# ads-b.net
KiCad netlist of a schematic drawn in EAGLE
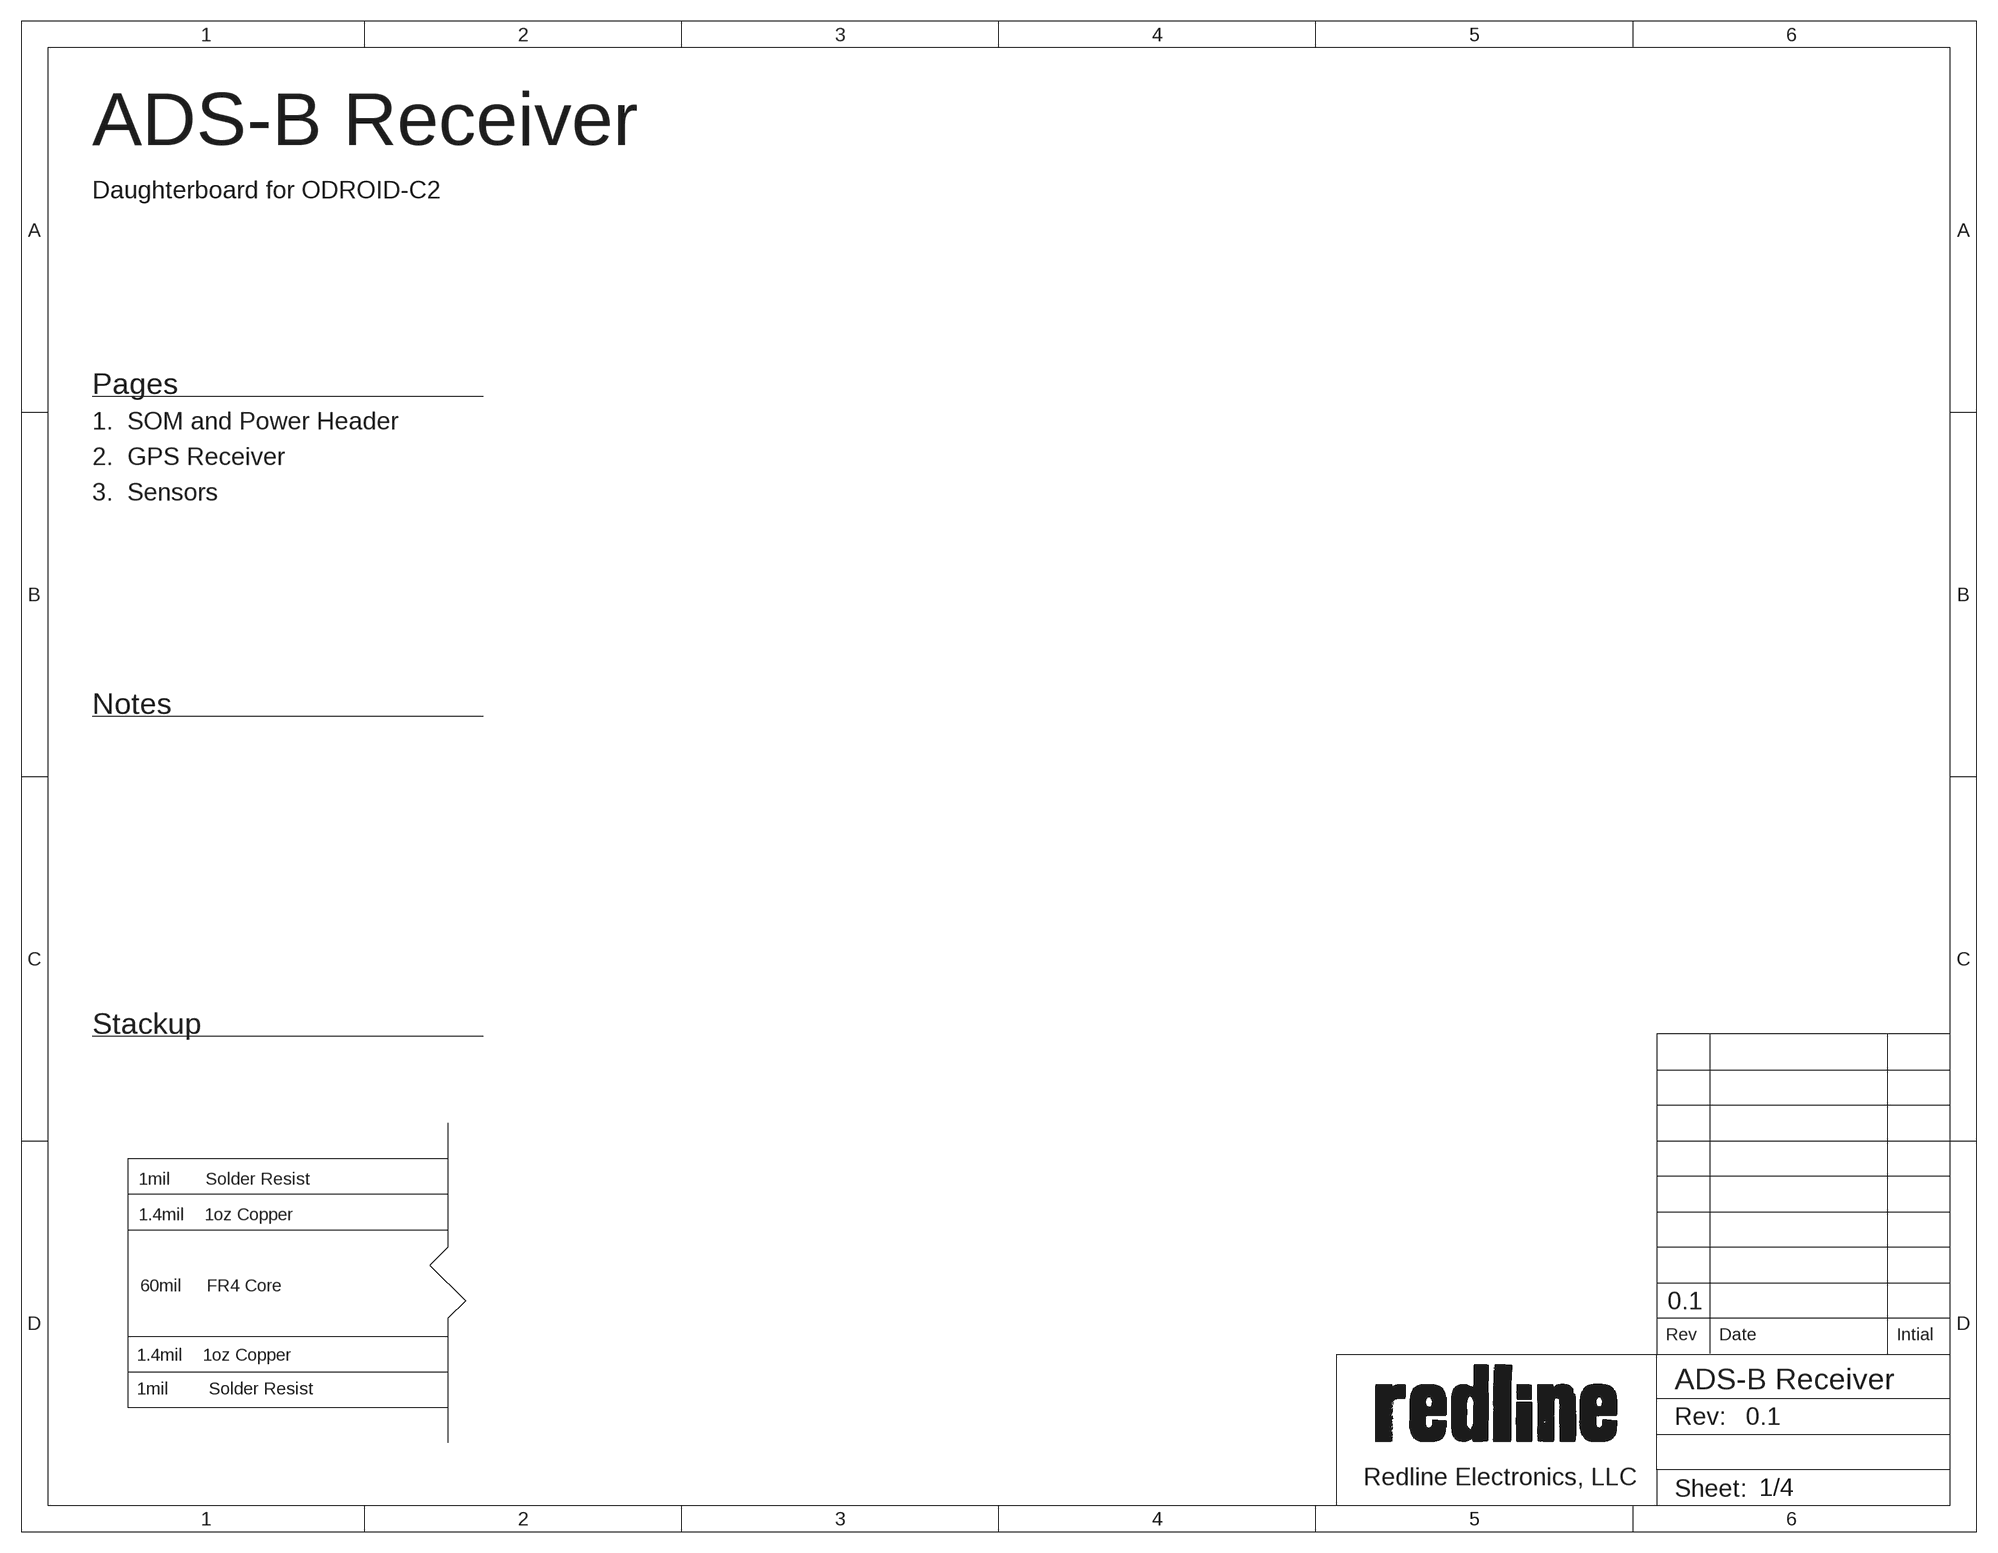
[diagram p0: schematic, sheet 1]
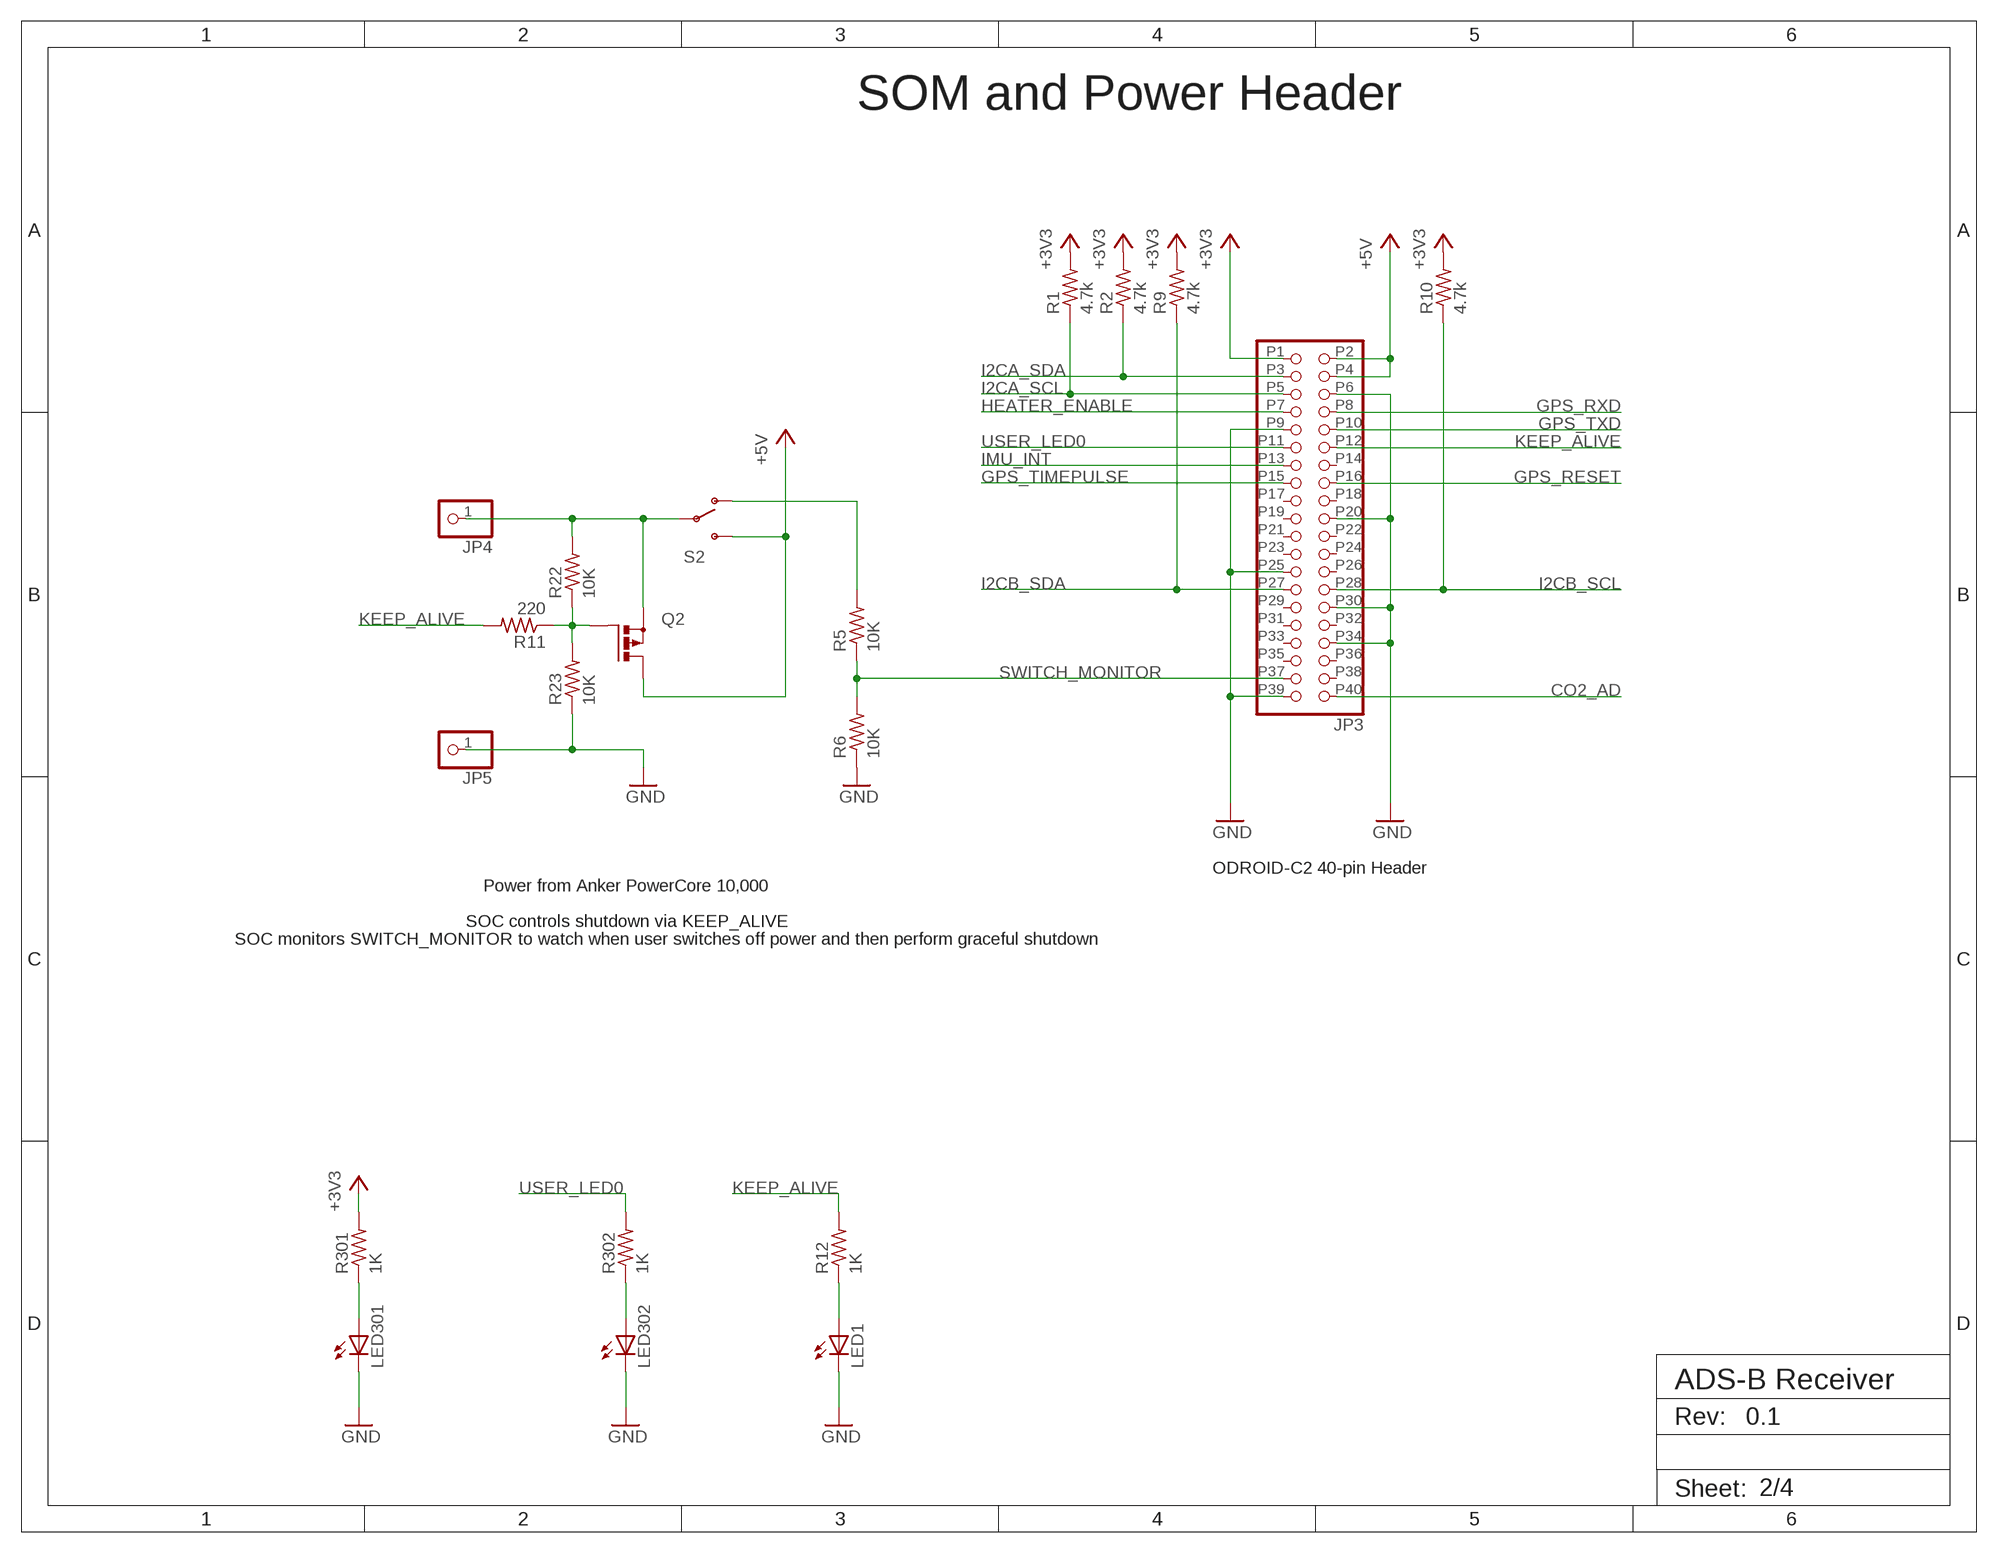
[diagram p1: schematic, sheet 2]
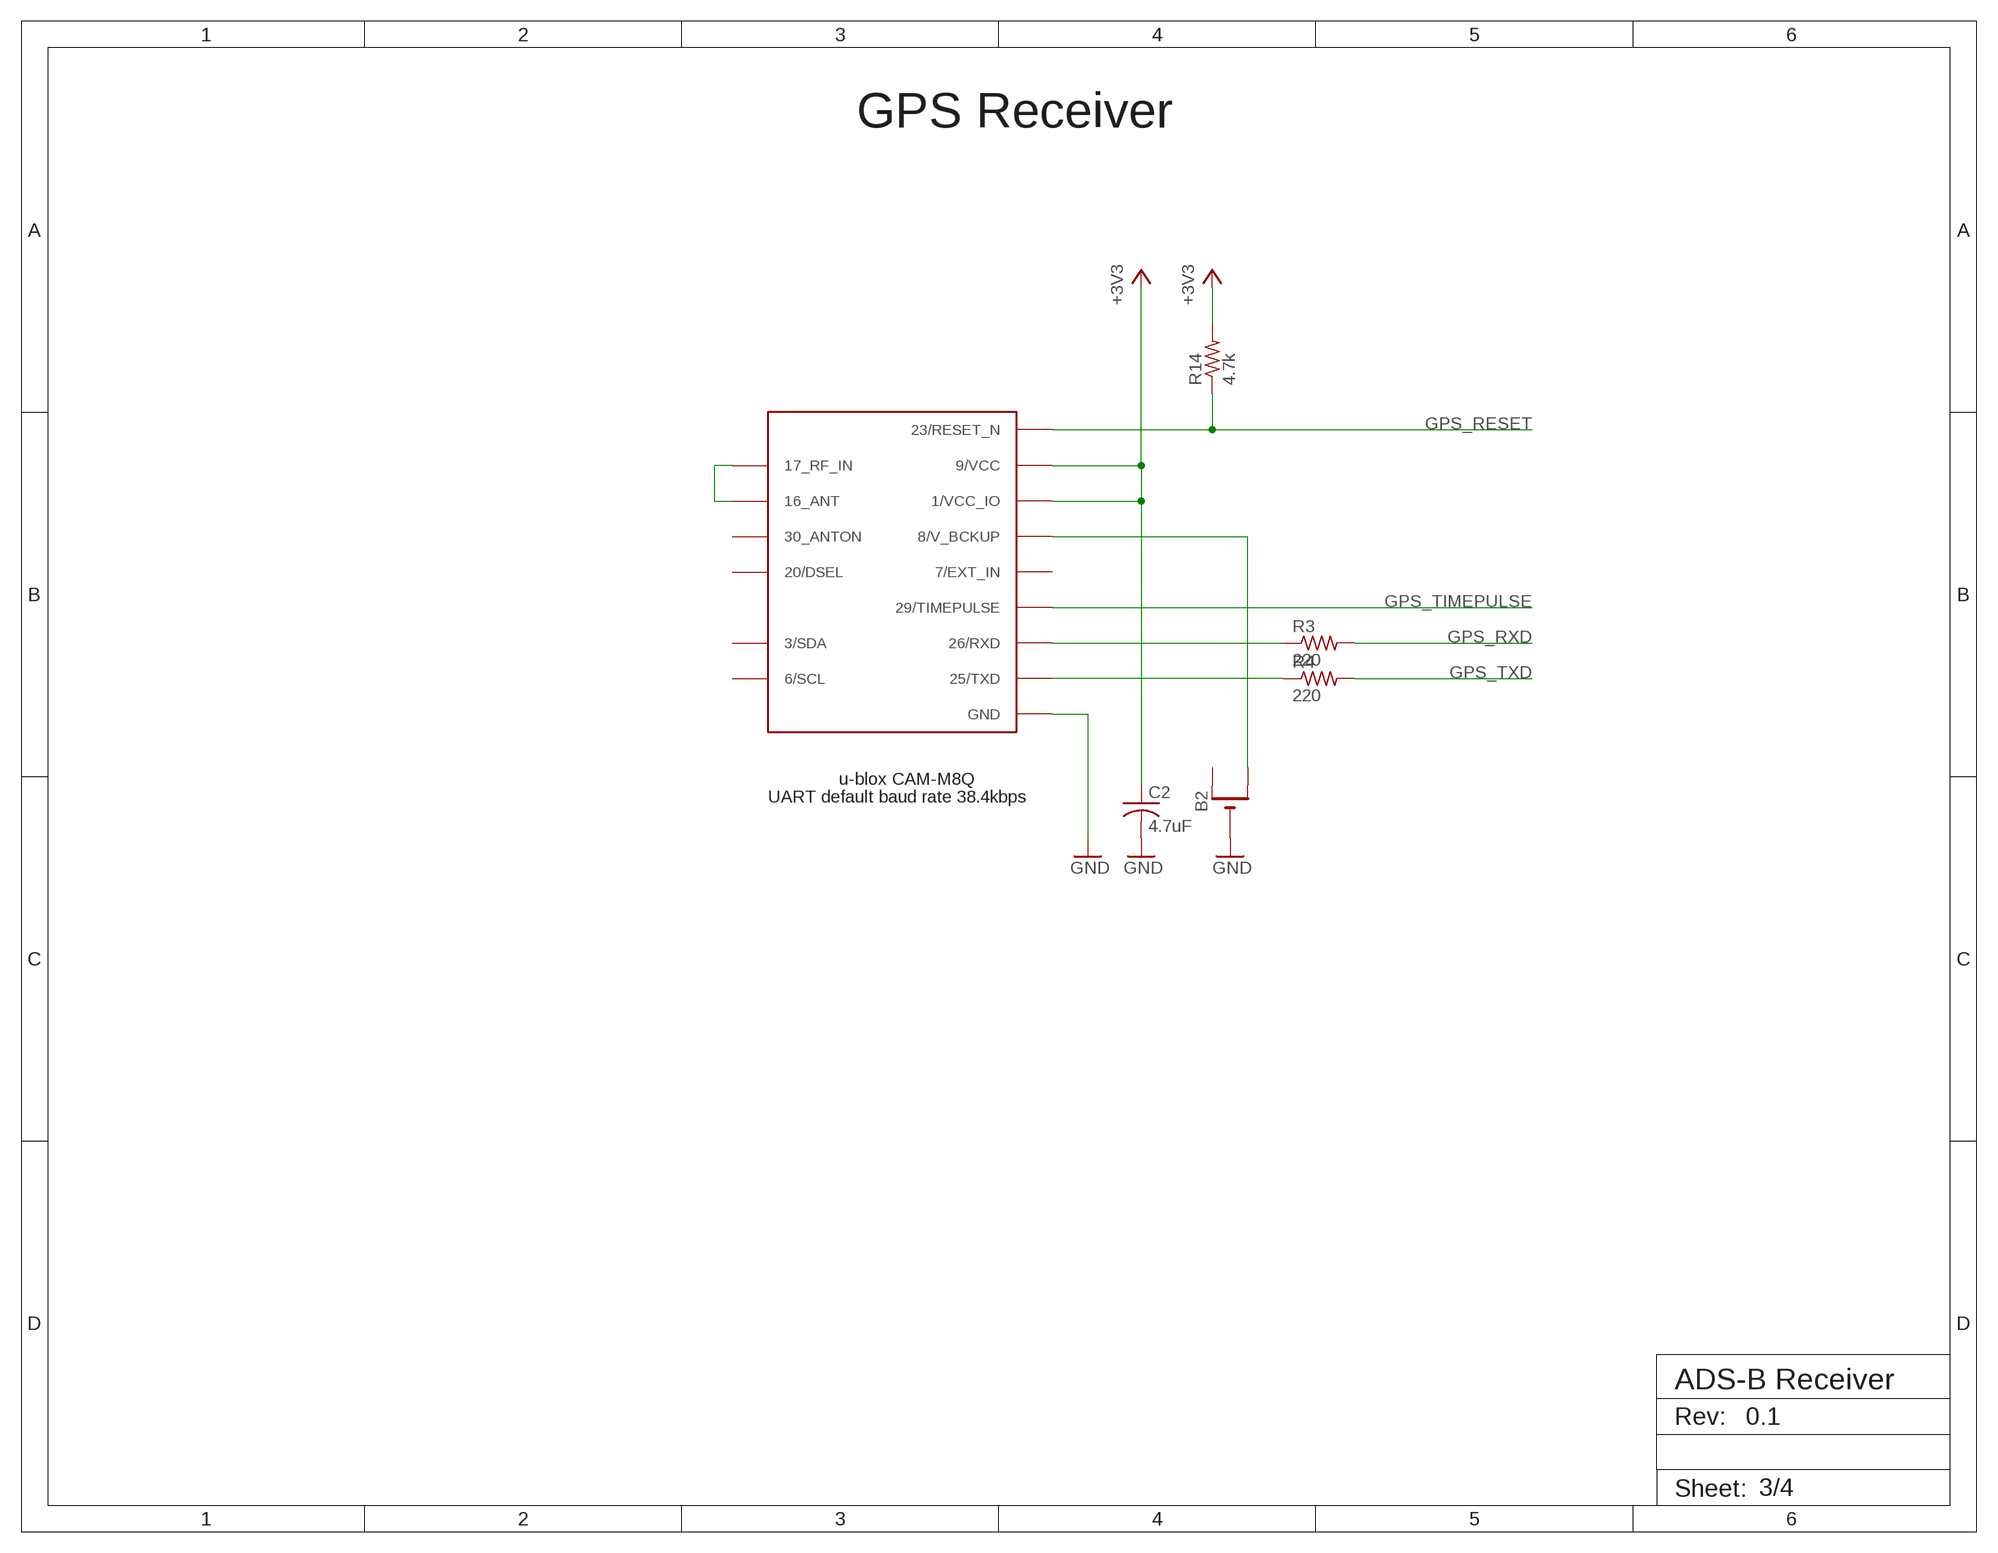
[diagram p2: schematic, sheet 3]
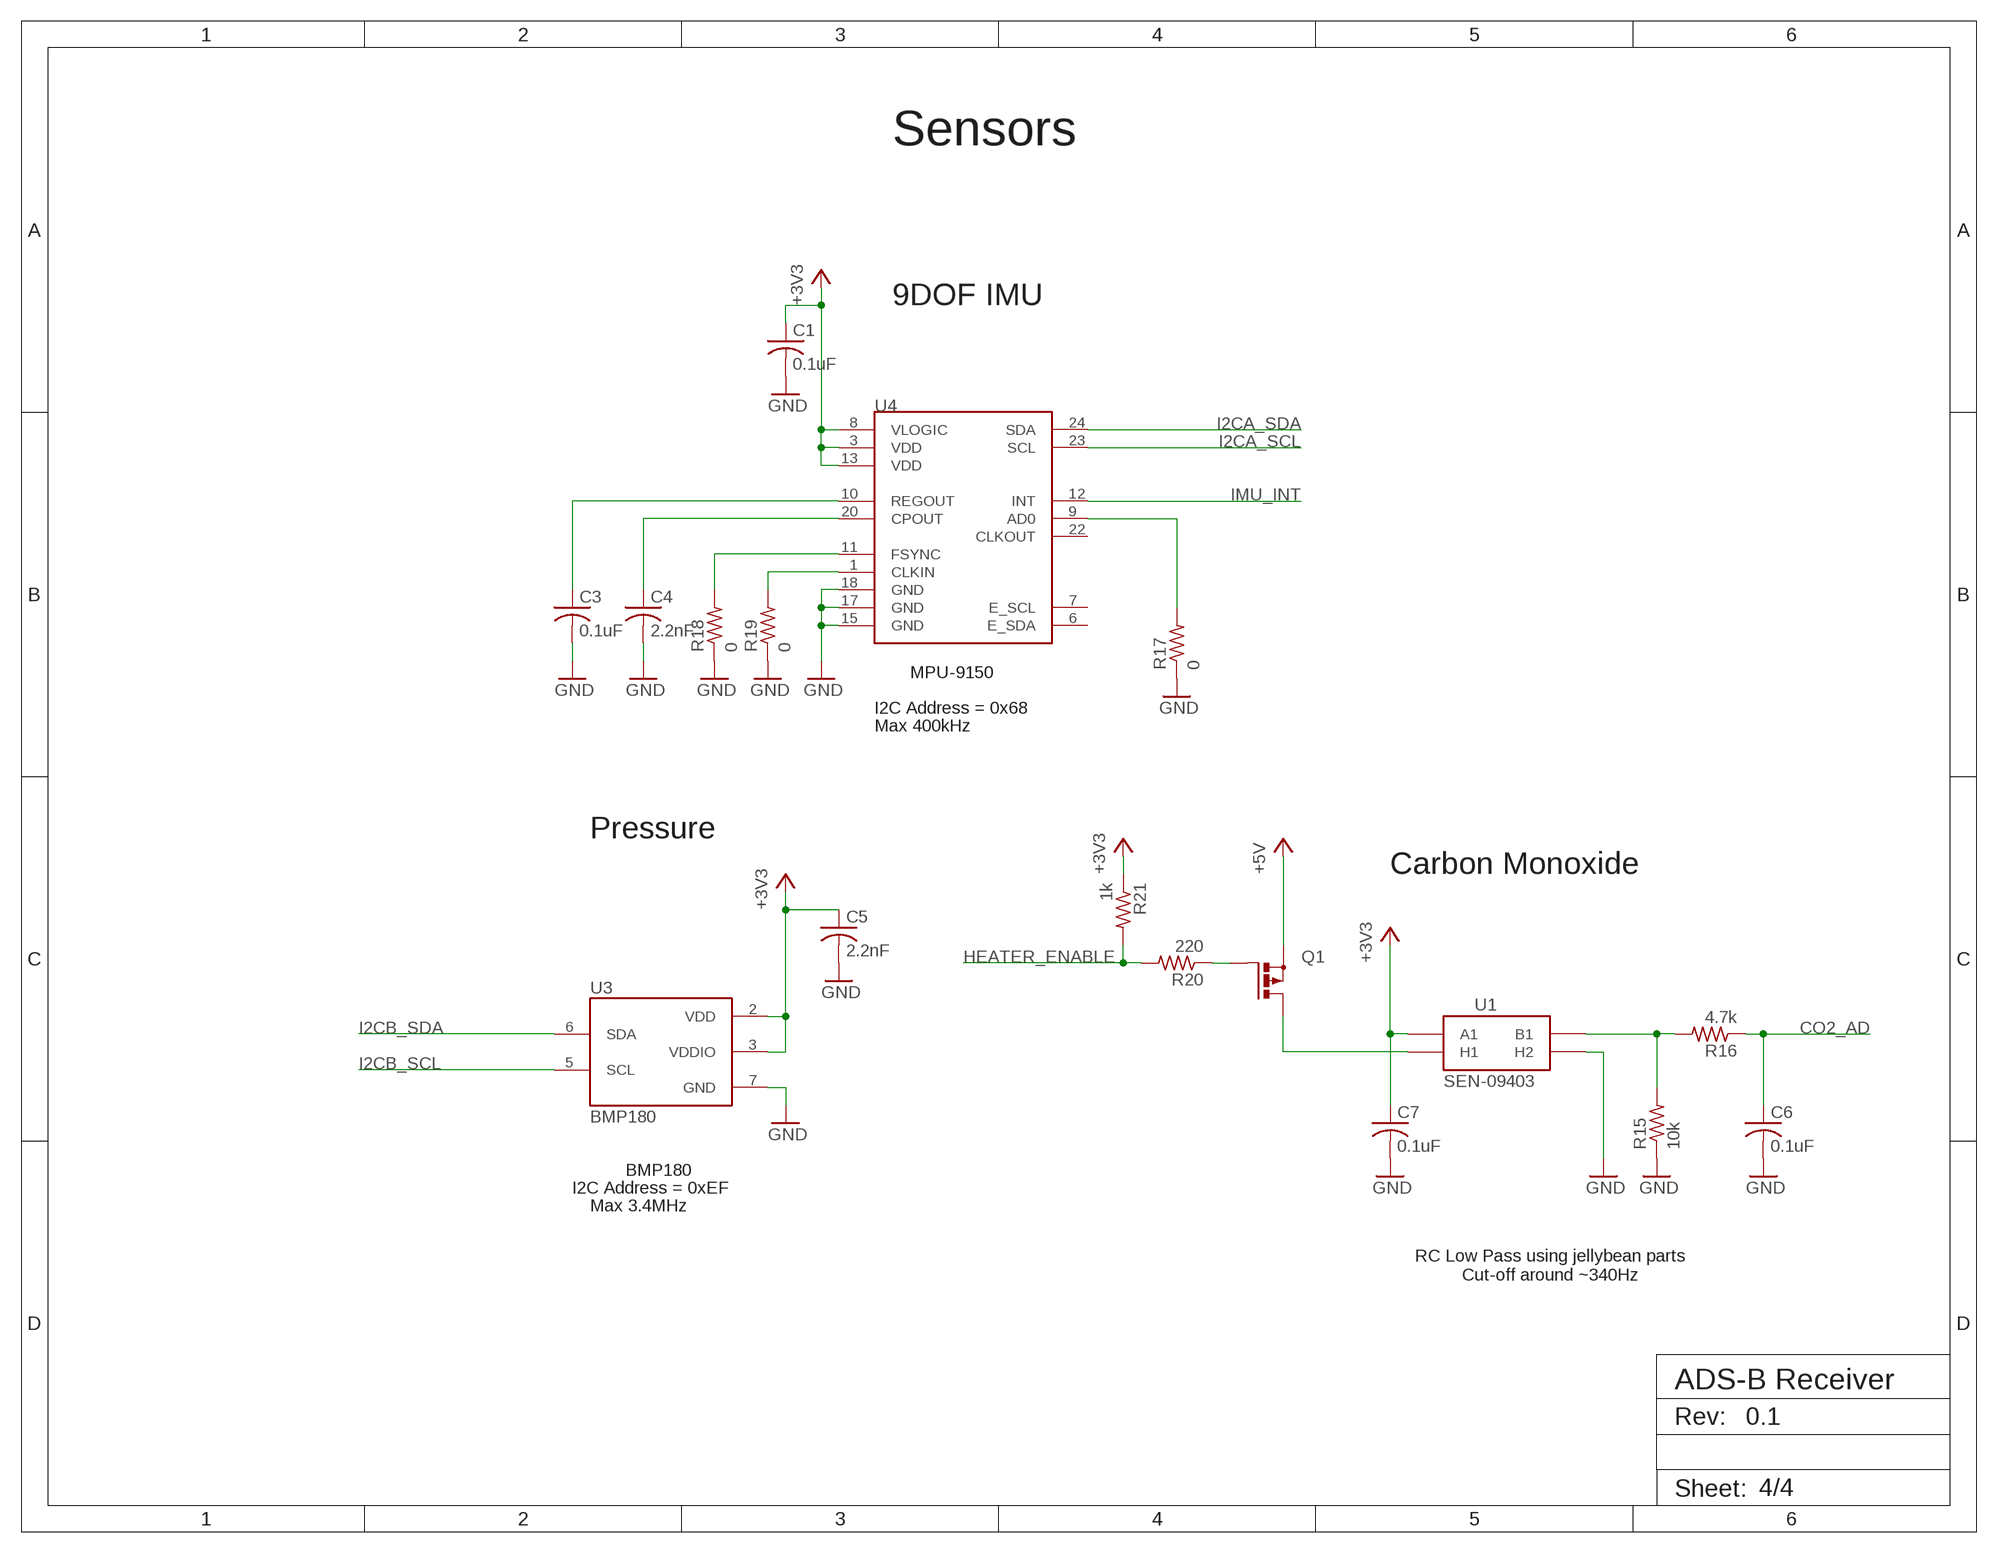
[diagram p3: schematic, sheet 4]

(export (version "E")
  (design (tool "Eeschema 10.0.6"))
  (components
    (comp (ref "B2")
      (value "CR1220THM")
      (footprint "eagle-import:CR1220-THM")
      (libsource (lib "eagle-import") (part "CR1220THM"))
    )
    (comp (ref "C2")
      (value "4.7uF")
      (footprint "eagle-import:C0603")
      (libsource (lib "eagle-import") (part "C-USC0603"))
    )
    (comp (ref "R3")
      (value "220")
      (footprint "eagle-import:R0603")
      (libsource (lib "eagle-import") (part "R-US_R0603"))
    )
    (comp (ref "R4")
      (value "220")
      (footprint "eagle-import:R0603")
      (libsource (lib "eagle-import") (part "R-US_R0603"))
    )
    (comp (ref "R14")
      (value "4.7k")
      (footprint "eagle-import:R0603")
      (libsource (lib "eagle-import") (part "R-US_R0603"))
    )
    (comp (ref "U$2")
      (value "UBLOX_CAM")
      (footprint "eagle-import:UBLOX_CAM")
      (libsource (lib "eagle-import") (part "UBLOX_CAM"))
    )
    (comp (ref "C1")
      (value "0.1uF")
      (footprint "eagle-import:C0603")
      (libsource (lib "eagle-import") (part "C-USC0603"))
    )
    (comp (ref "C3")
      (value "0.1uF")
      (footprint "eagle-import:C0603")
      (libsource (lib "eagle-import") (part "C-USC0603"))
    )
    (comp (ref "C4")
      (value "2.2nF")
      (footprint "eagle-import:C0603")
      (libsource (lib "eagle-import") (part "C-USC0603"))
    )
    (comp (ref "C5")
      (value "2.2nF")
      (footprint "eagle-import:C0603")
      (libsource (lib "eagle-import") (part "C-USC0603"))
    )
    (comp (ref "C6")
      (value "0.1uF")
      (footprint "eagle-import:C0603")
      (libsource (lib "eagle-import") (part "C-USC0603"))
    )
    (comp (ref "C7")
      (value "0.1uF")
      (footprint "eagle-import:C0603")
      (libsource (lib "eagle-import") (part "C-USC0603"))
    )
    (comp (ref "Q1")
      (value "P-MOSFET-SO8")
      (footprint "eagle-import:SO-08")
      (libsource (lib "eagle-import") (part "P-MOSFET-SO8"))
    )
    (comp (ref "R15")
      (value "10k")
      (footprint "eagle-import:R0603")
      (libsource (lib "eagle-import") (part "R-US_R0603"))
    )
    (comp (ref "R16")
      (value "4.7k")
      (footprint "eagle-import:R0603")
      (libsource (lib "eagle-import") (part "R-US_R0603"))
    )
    (comp (ref "R17")
      (value "0")
      (footprint "eagle-import:R0603")
      (libsource (lib "eagle-import") (part "R-US_R0603"))
    )
    (comp (ref "R18")
      (value "0")
      (footprint "eagle-import:R0603")
      (libsource (lib "eagle-import") (part "R-US_R0603"))
    )
    (comp (ref "R19")
      (value "0")
      (footprint "eagle-import:R0603")
      (libsource (lib "eagle-import") (part "R-US_R0603"))
    )
    (comp (ref "R20")
      (value "220")
      (footprint "eagle-import:R0603")
      (libsource (lib "eagle-import") (part "R-US_R0603"))
    )
    (comp (ref "R21")
      (value "1k")
      (footprint "eagle-import:R0603")
      (libsource (lib "eagle-import") (part "R-US_R0603"))
    )
    (comp (ref "U1")
      (value "SEN-09403")
      (footprint "eagle-import:MQ-3")
      (libsource (lib "eagle-import") (part "GAS_SENSOR"))
    )
    (comp (ref "U3")
      (value "BMP180")
      (footprint "eagle-import:BMP180")
      (libsource (lib "eagle-import") (part "BMP180"))
    )
    (comp (ref "U4")
      (value "MPU-9150QFN-24-NP")
      (footprint "eagle-import:QFN-24-NP")
      (libsource (lib "eagle-import") (part "MPU-9150QFN-24-NP"))
    )
    (comp (ref "JP3")
      (value "ODROID-C2")
      (footprint "eagle-import:2X20")
      (libsource (lib "eagle-import") (part "ODROID-C2"))
    )
    (comp (ref "JP4")
      (value "PINHD-1X1")
      (footprint "eagle-import:1X01")
      (libsource (lib "eagle-import") (part "PINHD-1X1"))
    )
    (comp (ref "JP5")
      (value "PINHD-1X1")
      (footprint "eagle-import:1X01")
      (libsource (lib "eagle-import") (part "PINHD-1X1"))
    )
    (comp (ref "LED1")
      (value "LEDSML0603")
      (footprint "eagle-import:SML0603")
      (libsource (lib "eagle-import") (part "LEDSML0603"))
    )
    (comp (ref "LED301")
      (value "LEDSML0603")
      (footprint "eagle-import:SML0603")
      (libsource (lib "eagle-import") (part "LEDSML0603"))
    )
    (comp (ref "LED302")
      (value "LEDSML0603")
      (footprint "eagle-import:SML0603")
      (libsource (lib "eagle-import") (part "LEDSML0603"))
    )
    (comp (ref "Q2")
      (value "P-MOSFET-SO8")
      (footprint "eagle-import:SO-08")
      (libsource (lib "eagle-import") (part "P-MOSFET-SO8"))
    )
    (comp (ref "R1")
      (value "4.7k")
      (footprint "eagle-import:R0603")
      (libsource (lib "eagle-import") (part "R-US_R0603"))
    )
    (comp (ref "R2")
      (value "4.7k")
      (footprint "eagle-import:R0603")
      (libsource (lib "eagle-import") (part "R-US_R0603"))
    )
    (comp (ref "R5")
      (value "10K")
      (footprint "eagle-import:R0603")
      (libsource (lib "eagle-import") (part "R-US_R0603"))
    )
    (comp (ref "R6")
      (value "10K")
      (footprint "eagle-import:R0603")
      (libsource (lib "eagle-import") (part "R-US_R0603"))
    )
    (comp (ref "R9")
      (value "4.7k")
      (footprint "eagle-import:R0603")
      (libsource (lib "eagle-import") (part "R-US_R0603"))
    )
    (comp (ref "R10")
      (value "4.7k")
      (footprint "eagle-import:R0603")
      (libsource (lib "eagle-import") (part "R-US_R0603"))
    )
    (comp (ref "R11")
      (value "220")
      (footprint "eagle-import:R0603")
      (libsource (lib "eagle-import") (part "R-US_R0603"))
    )
    (comp (ref "R12")
      (value "1K")
      (footprint "eagle-import:R0603")
      (libsource (lib "eagle-import") (part "R-US_R0603"))
    )
    (comp (ref "R22")
      (value "10K")
      (footprint "eagle-import:R0603")
      (libsource (lib "eagle-import") (part "R-US_R0603"))
    )
    (comp (ref "R23")
      (value "10K")
      (footprint "eagle-import:R0603")
      (libsource (lib "eagle-import") (part "R-US_R0603"))
    )
    (comp (ref "R301")
      (value "1K")
      (footprint "eagle-import:R0603")
      (libsource (lib "eagle-import") (part "R-US_R0603"))
    )
    (comp (ref "R302")
      (value "1K")
      (footprint "eagle-import:R0603")
      (libsource (lib "eagle-import") (part "R-US_R0603"))
    )
    (comp (ref "S2")
      (value "SWITCH-SPDTSMD2")
      (footprint "eagle-import:SWITCH-SPDT-SMD")
      (libsource (lib "eagle-import") (part "SWITCH-SPDTSMD2"))
    )
  )
  (nets
    (net (code "1") (name "+3V3") (class "Default")
      (node (ref "C1") (pin "1") (pinfunction "1_1") (pintype "passive"))
      (node (ref "C2") (pin "1") (pinfunction "1_1") (pintype "passive"))
      (node (ref "C5") (pin "1") (pinfunction "1_1") (pintype "passive"))
      (node (ref "C7") (pin "1") (pinfunction "1_1") (pintype "passive"))
      (node (ref "JP3") (pin "P1") (pinfunction "40_P1") (pintype "passive"))
      (node (ref "R1") (pin "2") (pinfunction "2_2") (pintype "passive"))
      (node (ref "R10") (pin "2") (pinfunction "2_2") (pintype "passive"))
      (node (ref "R14") (pin "2") (pinfunction "2_2") (pintype "passive"))
      (node (ref "R2") (pin "2") (pinfunction "2_2") (pintype "passive"))
      (node (ref "R21") (pin "1") (pinfunction "1_1") (pintype "passive"))
      (node (ref "R301") (pin "2") (pinfunction "2_2") (pintype "passive"))
      (node (ref "R9") (pin "2") (pinfunction "2_2") (pintype "passive"))
      (node (ref "U$2") (pin "1/VCC_IO") (pinfunction "1/VCC_IO_1/VCC_IO") (pintype "power_in"))
      (node (ref "U$2") (pin "9/VCC") (pinfunction "9/VCC_9/VCC") (pintype "power_in"))
      (node (ref "U1") (pin "A1") (pinfunction "A1_A1") (pintype "bidirectional"))
      (node (ref "U3") (pin "2") (pinfunction "VDD_2") (pintype "power_in"))
      (node (ref "U3") (pin "3") (pinfunction "VDDIO_3") (pintype "power_in"))
      (node (ref "U4") (pin "13") (pinfunction "VDD_13") (pintype "bidirectional"))
      (node (ref "U4") (pin "3") (pinfunction "VDD_3") (pintype "bidirectional"))
      (node (ref "U4") (pin "8") (pinfunction "VLOGIC_8") (pintype "bidirectional"))
    )
    (net (code "2") (name "+5V") (class "Default")
      (node (ref "JP3") (pin "P2") (pinfunction "39_P2") (pintype "passive"))
      (node (ref "JP3") (pin "P4") (pinfunction "37_P4") (pintype "passive"))
      (node (ref "Q1") (pin "1") (pinfunction "S_1") (pintype "passive"))
      (node (ref "Q1") (pin "2") (pinfunction "S_2") (pintype "passive"))
      (node (ref "Q1") (pin "3") (pinfunction "S_3") (pintype "passive"))
      (node (ref "Q2") (pin "5") (pinfunction "D_5") (pintype "passive"))
      (node (ref "Q2") (pin "6") (pinfunction "D_6") (pintype "passive"))
      (node (ref "Q2") (pin "7") (pinfunction "D_7") (pintype "passive"))
      (node (ref "Q2") (pin "8") (pinfunction "D_8") (pintype "passive"))
      (node (ref "S2") (pin "3") (pinfunction "S_3") (pintype "passive"))
    )
    (net (code "3") (name "CO2_AD") (class "Default")
      (node (ref "C6") (pin "1") (pinfunction "1_1") (pintype "passive"))
      (node (ref "JP3") (pin "P40") (pinfunction "1_P40") (pintype "passive"))
      (node (ref "R16") (pin "1") (pinfunction "1_1") (pintype "passive"))
    )
    (net (code "4") (name "GND") (class "Default")
      (node (ref "B2") (pin "-") (pinfunction "-_-") (pintype "passive"))
      (node (ref "C1") (pin "2") (pinfunction "2_2") (pintype "passive"))
      (node (ref "C2") (pin "2") (pinfunction "2_2") (pintype "passive"))
      (node (ref "C3") (pin "2") (pinfunction "2_2") (pintype "passive"))
      (node (ref "C4") (pin "2") (pinfunction "2_2") (pintype "passive"))
      (node (ref "C5") (pin "2") (pinfunction "2_2") (pintype "passive"))
      (node (ref "C6") (pin "2") (pinfunction "2_2") (pintype "passive"))
      (node (ref "C7") (pin "2") (pinfunction "2_2") (pintype "passive"))
      (node (ref "JP3") (pin "P20") (pinfunction "21_P20") (pintype "passive"))
      (node (ref "JP3") (pin "P25") (pinfunction "16_P25") (pintype "passive"))
      (node (ref "JP3") (pin "P30") (pinfunction "11_P30") (pintype "passive"))
      (node (ref "JP3") (pin "P34") (pinfunction "7_P34") (pintype "passive"))
      (node (ref "JP3") (pin "P39") (pinfunction "2_P39") (pintype "passive"))
      (node (ref "JP3") (pin "P6") (pinfunction "35_P6") (pintype "passive"))
      (node (ref "JP3") (pin "P9") (pinfunction "32_P9") (pintype "passive"))
      (node (ref "JP5") (pin "1") (pinfunction "1_1") (pintype "passive"))
      (node (ref "LED1") (pin "C") (pinfunction "C_C") (pintype "passive"))
      (node (ref "LED301") (pin "C") (pinfunction "C_C") (pintype "passive"))
      (node (ref "LED302") (pin "C") (pinfunction "C_C") (pintype "passive"))
      (node (ref "R15") (pin "1") (pinfunction "1_1") (pintype "passive"))
      (node (ref "R17") (pin "1") (pinfunction "1_1") (pintype "passive"))
      (node (ref "R18") (pin "1") (pinfunction "1_1") (pintype "passive"))
      (node (ref "R19") (pin "1") (pinfunction "1_1") (pintype "passive"))
      (node (ref "R23") (pin "1") (pinfunction "1_1") (pintype "passive"))
      (node (ref "R6") (pin "1") (pinfunction "1_1") (pintype "passive"))
      (node (ref "U$2") (pin "10/GND") (pinfunction "GND_10/GND") (pintype "power_in"))
      (node (ref "U$2") (pin "11/GND") (pinfunction "GND_11/GND") (pintype "power_in"))
      (node (ref "U$2") (pin "12/GND") (pinfunction "GND_12/GND") (pintype "power_in"))
      (node (ref "U$2") (pin "13/GND") (pinfunction "GND_13/GND") (pintype "power_in"))
      (node (ref "U$2") (pin "14/GND") (pinfunction "GND_14/GND") (pintype "power_in"))
      (node (ref "U$2") (pin "15/GND") (pinfunction "GND_15/GND") (pintype "power_in"))
      (node (ref "U$2") (pin "18/GND") (pinfunction "GND_18/GND") (pintype "power_in"))
      (node (ref "U$2") (pin "19/GND") (pinfunction "GND_19/GND") (pintype "power_in"))
      (node (ref "U$2") (pin "21/GND") (pinfunction "GND_21/GND") (pintype "power_in"))
      (node (ref "U$2") (pin "22/GND") (pinfunction "GND_22/GND") (pintype "power_in"))
      (node (ref "U$2") (pin "27/GND") (pinfunction "GND_27/GND") (pintype "power_in"))
      (node (ref "U$2") (pin "31/GND") (pinfunction "GND_31/GND") (pintype "power_in"))
      (node (ref "U$2") (pin "4/GND") (pinfunction "GND_4/GND") (pintype "power_in"))
      (node (ref "U$2") (pin "5/GND") (pinfunction "GND_5/GND") (pintype "power_in"))
      (node (ref "U1") (pin "HB") (pinfunction "H2_HB") (pintype "bidirectional"))
      (node (ref "U3") (pin "7") (pinfunction "GND_7") (pintype "power_in"))
      (node (ref "U4") (pin "15") (pinfunction "GND_15") (pintype "bidirectional"))
      (node (ref "U4") (pin "17") (pinfunction "GND_17") (pintype "bidirectional"))
      (node (ref "U4") (pin "18") (pinfunction "GND_18") (pintype "bidirectional"))
    )
    (net (code "5") (name "GPS_RESET") (class "Default")
      (node (ref "JP3") (pin "P16") (pinfunction "25_P16") (pintype "passive"))
      (node (ref "R14") (pin "1") (pinfunction "1_1") (pintype "passive"))
      (node (ref "U$2") (pin "23/RESET_N") (pinfunction "23/RESET_N_23/RESET_N") (pintype "power_in"))
    )
    (net (code "6") (name "GPS_RXD") (class "Default")
      (node (ref "JP3") (pin "P8") (pinfunction "33_P8") (pintype "passive"))
      (node (ref "R3") (pin "2") (pinfunction "2_2") (pintype "passive"))
    )
    (net (code "7") (name "GPS_TIMEPULSE") (class "Default")
      (node (ref "JP3") (pin "P15") (pinfunction "26_P15") (pintype "passive"))
      (node (ref "U$2") (pin "29/TIMEPULSE") (pinfunction "29/TIMEPULSE_29/TIMEPULSE") (pintype "bidirectional"))
    )
    (net (code "8") (name "GPS_TXD") (class "Default")
      (node (ref "JP3") (pin "P10") (pinfunction "31_P10") (pintype "passive"))
      (node (ref "R4") (pin "2") (pinfunction "2_2") (pintype "passive"))
    )
    (net (code "9") (name "HEATER_ENABLE") (class "Default")
      (node (ref "JP3") (pin "P7") (pinfunction "34_P7") (pintype "passive"))
      (node (ref "R20") (pin "2") (pinfunction "2_2") (pintype "passive"))
      (node (ref "R21") (pin "2") (pinfunction "2_2") (pintype "passive"))
    )
    (net (code "10") (name "I2CA_SCL") (class "Default")
      (node (ref "JP3") (pin "P5") (pinfunction "36_P5") (pintype "passive"))
      (node (ref "R1") (pin "1") (pinfunction "1_1") (pintype "passive"))
      (node (ref "U4") (pin "23") (pinfunction "SCL_23") (pintype "bidirectional"))
    )
    (net (code "11") (name "I2CA_SDA") (class "Default")
      (node (ref "JP3") (pin "P3") (pinfunction "38_P3") (pintype "passive"))
      (node (ref "R2") (pin "1") (pinfunction "1_1") (pintype "passive"))
      (node (ref "U4") (pin "24") (pinfunction "SDA_24") (pintype "bidirectional"))
    )
    (net (code "12") (name "I2CB_SCL") (class "Default")
      (node (ref "JP3") (pin "P28") (pinfunction "13_P28") (pintype "passive"))
      (node (ref "R10") (pin "1") (pinfunction "1_1") (pintype "passive"))
      (node (ref "U3") (pin "5") (pinfunction "SCL_5") (pintype "input"))
    )
    (net (code "13") (name "I2CB_SDA") (class "Default")
      (node (ref "JP3") (pin "P27") (pinfunction "14_P27") (pintype "passive"))
      (node (ref "R9") (pin "1") (pinfunction "1_1") (pintype "passive"))
      (node (ref "U3") (pin "6") (pinfunction "SDA_6") (pintype "bidirectional"))
    )
    (net (code "14") (name "IMU_INT") (class "Default")
      (node (ref "JP3") (pin "P13") (pinfunction "28_P13") (pintype "passive"))
      (node (ref "U4") (pin "12") (pinfunction "INT_12") (pintype "bidirectional"))
    )
    (net (code "15") (name "KEEP_ALIVE") (class "Default")
      (node (ref "JP3") (pin "P12") (pinfunction "29_P12") (pintype "passive"))
      (node (ref "R11") (pin "2") (pinfunction "2_2") (pintype "passive"))
      (node (ref "R12") (pin "2") (pinfunction "2_2") (pintype "passive"))
    )
    (net (code "16") (name "Net-(B2-+1)") (class "Default")
      (node (ref "B2") (pin "+2") (pinfunction "+1_+2") (pintype "passive"))
      (node (ref "U$2") (pin "8/V_BCKP") (pinfunction "8/V_BCKUP_8/V_BCKP") (pintype "bidirectional"))
    )
    (net (code "17") (name "Net-(LED1-PadA)") (class "Default")
      (node (ref "LED1") (pin "A") (pinfunction "A_A") (pintype "passive"))
      (node (ref "R12") (pin "1") (pinfunction "1_1") (pintype "passive"))
    )
    (net (code "18") (name "Net-(LED301-PadA)") (class "Default")
      (node (ref "LED301") (pin "A") (pinfunction "A_A") (pintype "passive"))
      (node (ref "R301") (pin "1") (pinfunction "1_1") (pintype "passive"))
    )
    (net (code "19") (name "Net-(LED302-PadA)") (class "Default")
      (node (ref "LED302") (pin "A") (pinfunction "A_A") (pintype "passive"))
      (node (ref "R302") (pin "1") (pinfunction "1_1") (pintype "passive"))
    )
    (net (code "20") (name "Net-(Q1-G)") (class "Default")
      (node (ref "Q1") (pin "4") (pinfunction "G_4") (pintype "passive"))
      (node (ref "R20") (pin "1") (pinfunction "1_1") (pintype "passive"))
    )
    (net (code "21") (name "Net-(Q2-G)") (class "Default")
      (node (ref "Q2") (pin "4") (pinfunction "G_4") (pintype "passive"))
      (node (ref "R11") (pin "1") (pinfunction "1_1") (pintype "passive"))
      (node (ref "R22") (pin "1") (pinfunction "1_1") (pintype "passive"))
      (node (ref "R23") (pin "2") (pinfunction "2_2") (pintype "passive"))
    )
    (net (code "22") (name "Net-(R3-Pad1)") (class "Default")
      (node (ref "R3") (pin "1") (pinfunction "1_1") (pintype "passive"))
      (node (ref "U$2") (pin "26/RXD") (pinfunction "26/RXD_26/RXD") (pintype "bidirectional"))
    )
    (net (code "23") (name "Net-(R4-Pad1)") (class "Default")
      (node (ref "R4") (pin "1") (pinfunction "1_1") (pintype "passive"))
      (node (ref "U$2") (pin "25/TXD") (pinfunction "25/TXD_25/TXD") (pintype "bidirectional"))
    )
    (net (code "24") (name "Net-(R15-Pad2)") (class "Default")
      (node (ref "R15") (pin "2") (pinfunction "2_2") (pintype "passive"))
      (node (ref "R16") (pin "2") (pinfunction "2_2") (pintype "passive"))
      (node (ref "U1") (pin "B1") (pinfunction "B1_B1") (pintype "bidirectional"))
    )
    (net (code "25") (name "Net-(S2-O)") (class "Default")
      (node (ref "R5") (pin "2") (pinfunction "2_2") (pintype "passive"))
      (node (ref "S2") (pin "1") (pinfunction "O_1") (pintype "passive"))
    )
    (net (code "26") (name "Net-(S2-P)") (class "Default")
      (node (ref "JP4") (pin "1") (pinfunction "1_1") (pintype "passive"))
      (node (ref "Q2") (pin "1") (pinfunction "S_1") (pintype "passive"))
      (node (ref "Q2") (pin "2") (pinfunction "S_2") (pintype "passive"))
      (node (ref "Q2") (pin "3") (pinfunction "S_3") (pintype "passive"))
      (node (ref "R22") (pin "2") (pinfunction "2_2") (pintype "passive"))
      (node (ref "S2") (pin "2") (pinfunction "P_2") (pintype "passive"))
    )
    (net (code "27") (name "Net-(U$2-16_ANT)") (class "Default")
      (node (ref "U$2") (pin "16/ANT") (pinfunction "16_ANT_16/ANT") (pintype "power_in"))
      (node (ref "U$2") (pin "17/RF_IN") (pinfunction "17_RF_IN_17/RF_IN") (pintype "bidirectional"))
    )
    (net (code "28") (name "Net-(U1-H1)") (class "Default")
      (node (ref "Q1") (pin "5") (pinfunction "D_5") (pintype "passive"))
      (node (ref "Q1") (pin "6") (pinfunction "D_6") (pintype "passive"))
      (node (ref "Q1") (pin "7") (pinfunction "D_7") (pintype "passive"))
      (node (ref "Q1") (pin "8") (pinfunction "D_8") (pintype "passive"))
      (node (ref "U1") (pin "HA") (pinfunction "H1_HA") (pintype "bidirectional"))
    )
    (net (code "29") (name "Net-(U4-AD0)") (class "Default")
      (node (ref "R17") (pin "2") (pinfunction "2_2") (pintype "passive"))
      (node (ref "U4") (pin "9") (pinfunction "AD0_9") (pintype "bidirectional"))
    )
    (net (code "30") (name "Net-(U4-CLKIN)") (class "Default")
      (node (ref "R19") (pin "2") (pinfunction "2_2") (pintype "passive"))
      (node (ref "U4") (pin "1") (pinfunction "CLKIN_1") (pintype "bidirectional"))
    )
    (net (code "31") (name "Net-(U4-CPOUT)") (class "Default")
      (node (ref "C4") (pin "1") (pinfunction "1_1") (pintype "passive"))
      (node (ref "U4") (pin "20") (pinfunction "CPOUT_20") (pintype "bidirectional"))
    )
    (net (code "32") (name "Net-(U4-FSYNC)") (class "Default")
      (node (ref "R18") (pin "2") (pinfunction "2_2") (pintype "passive"))
      (node (ref "U4") (pin "11") (pinfunction "FSYNC_11") (pintype "bidirectional"))
    )
    (net (code "33") (name "Net-(U4-REGOUT)") (class "Default")
      (node (ref "C3") (pin "1") (pinfunction "1_1") (pintype "passive"))
      (node (ref "U4") (pin "10") (pinfunction "REGOUT_10") (pintype "bidirectional"))
    )
    (net (code "34") (name "SWITCH_MONITOR") (class "Default")
      (node (ref "JP3") (pin "P37") (pinfunction "4_P37") (pintype "passive"))
      (node (ref "R5") (pin "1") (pinfunction "1_1") (pintype "passive"))
      (node (ref "R6") (pin "2") (pinfunction "2_2") (pintype "passive"))
    )
    (net (code "35") (name "USER_LED0") (class "Default")
      (node (ref "JP3") (pin "P11") (pinfunction "30_P11") (pintype "passive"))
      (node (ref "R302") (pin "2") (pinfunction "2_2") (pintype "passive"))
    )
    (net (code "36") (name "unconnected-(B2-+-Pad+1)") (class "Default")
      (node (ref "B2") (pin "+1") (pinfunction "+_+1") (pintype "passive"))
    )
    (net (code "37") (name "unconnected-(JP3-3-PadP38)") (class "Default")
      (node (ref "JP3") (pin "P38") (pinfunction "3_P38") (pintype "passive"))
    )
    (net (code "38") (name "unconnected-(JP3-5-PadP36)") (class "Default")
      (node (ref "JP3") (pin "P36") (pinfunction "5_P36") (pintype "passive"))
    )
    (net (code "39") (name "unconnected-(JP3-6-PadP35)") (class "Default")
      (node (ref "JP3") (pin "P35") (pinfunction "6_P35") (pintype "passive"))
    )
    (net (code "40") (name "unconnected-(JP3-8-PadP33)") (class "Default")
      (node (ref "JP3") (pin "P33") (pinfunction "8_P33") (pintype "passive"))
    )
    (net (code "41") (name "unconnected-(JP3-9-PadP32)") (class "Default")
      (node (ref "JP3") (pin "P32") (pinfunction "9_P32") (pintype "passive"))
    )
    (net (code "42") (name "unconnected-(JP3-10-PadP31)") (class "Default")
      (node (ref "JP3") (pin "P31") (pinfunction "10_P31") (pintype "passive"))
    )
    (net (code "43") (name "unconnected-(JP3-12-PadP29)") (class "Default")
      (node (ref "JP3") (pin "P29") (pinfunction "12_P29") (pintype "passive"))
    )
    (net (code "44") (name "unconnected-(JP3-15-PadP26)") (class "Default")
      (node (ref "JP3") (pin "P26") (pinfunction "15_P26") (pintype "passive"))
    )
    (net (code "45") (name "unconnected-(JP3-17-PadP24)") (class "Default")
      (node (ref "JP3") (pin "P24") (pinfunction "17_P24") (pintype "passive"))
    )
    (net (code "46") (name "unconnected-(JP3-18-PadP23)") (class "Default")
      (node (ref "JP3") (pin "P23") (pinfunction "18_P23") (pintype "passive"))
    )
    (net (code "47") (name "unconnected-(JP3-19-PadP22)") (class "Default")
      (node (ref "JP3") (pin "P22") (pinfunction "19_P22") (pintype "passive"))
    )
    (net (code "48") (name "unconnected-(JP3-20-PadP21)") (class "Default")
      (node (ref "JP3") (pin "P21") (pinfunction "20_P21") (pintype "passive"))
    )
    (net (code "49") (name "unconnected-(JP3-22-PadP19)") (class "Default")
      (node (ref "JP3") (pin "P19") (pinfunction "22_P19") (pintype "passive"))
    )
    (net (code "50") (name "unconnected-(JP3-23-PadP18)") (class "Default")
      (node (ref "JP3") (pin "P18") (pinfunction "23_P18") (pintype "passive"))
    )
    (net (code "51") (name "unconnected-(JP3-24-PadP17)") (class "Default")
      (node (ref "JP3") (pin "P17") (pinfunction "24_P17") (pintype "passive"))
    )
    (net (code "52") (name "unconnected-(JP3-27-PadP14)") (class "Default")
      (node (ref "JP3") (pin "P14") (pinfunction "27_P14") (pintype "passive"))
    )
    (net (code "53") (name "unconnected-(U$2-7{slash}EXT_IN-Pad7{slash}EXINT)") (class "Default")
      (node (ref "U$2") (pin "7/EXINT") (pinfunction "7/EXT_IN_7/EXINT") (pintype "bidirectional"))
    )
    (net (code "54") (name "unconnected-(U$2-30_ANTON-Pad30{slash}ANTON)") (class "Default")
      (node (ref "U$2") (pin "30/ANTON") (pinfunction "30_ANTON_30/ANTON") (pintype "bidirectional"))
    )
    (net (code "55") (name "unconnected-(U$2-Pad3{slash}SDA)") (class "Default")
      (node (ref "U$2") (pin "3/SDA") (pinfunction "3/SDA_3/SDA") (pintype "bidirectional"))
    )
    (net (code "56") (name "unconnected-(U$2-Pad6{slash}SCL)") (class "Default")
      (node (ref "U$2") (pin "6/SCL") (pinfunction "6/SCL_6/SCL") (pintype "bidirectional"))
    )
    (net (code "57") (name "unconnected-(U$2-Pad20{slash}DSEL)") (class "Default")
      (node (ref "U$2") (pin "20/DSEL") (pinfunction "20/DSEL_20/DSEL") (pintype "bidirectional"))
    )
    (net (code "58") (name "unconnected-(U4-CLKOUT-Pad22)") (class "Default")
      (node (ref "U4") (pin "22") (pinfunction "CLKOUT_22") (pintype "bidirectional"))
    )
    (net (code "59") (name "unconnected-(U4-E_SCL-Pad7)") (class "Default")
      (node (ref "U4") (pin "7") (pinfunction "E_SCL_7") (pintype "bidirectional"))
    )
    (net (code "60") (name "unconnected-(U4-E_SDA-Pad6)") (class "Default")
      (node (ref "U4") (pin "6") (pinfunction "E_SDA_6") (pintype "bidirectional"))
    )
  )
)
